# CommitV1_0.net
KiCad netlist of a schematic drawn in Altium Designer
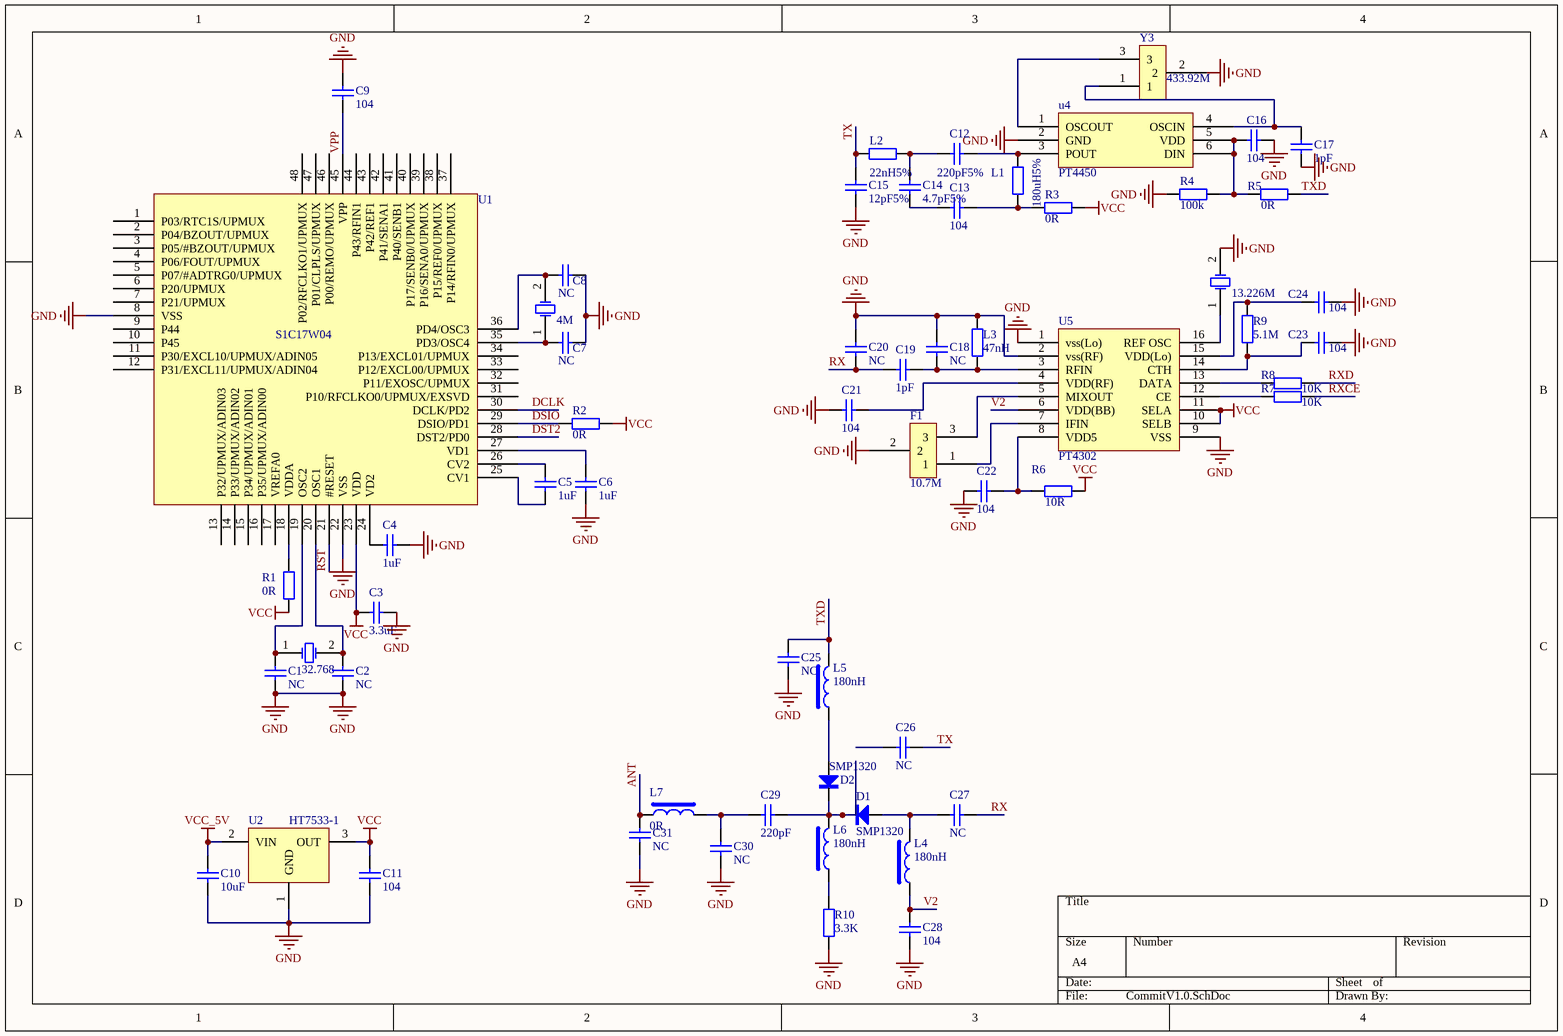
[diagram p0: CommitV1.0.SchDoc]

(export (version "E")
  (design (tool "Eeschema 10.0.6"))
  (components
    (comp (ref "C1")
      (value "NC")
      (footprint "0603")
      (description "Capacitor")
      (fields (field (name "PUBLISHER") "Altium Limited"))
      (libsource (lib "Miscellaneous Devices") (part "Cap"))
    )
    (comp (ref "C2")
      (value "NC")
      (footprint "0603")
      (description "Capacitor")
      (fields (field (name "PUBLISHER") "Altium Limited"))
      (libsource (lib "Miscellaneous Devices") (part "Cap"))
    )
    (comp (ref "C3")
      (value "3.3uF")
      (footprint "0603")
      (description "Capacitor")
      (fields (field (name "PUBLISHER") "Altium Limited"))
      (libsource (lib "Miscellaneous Devices") (part "Cap"))
    )
    (comp (ref "C4")
      (value "1uF")
      (footprint "0603")
      (description "Capacitor")
      (fields (field (name "PUBLISHER") "Altium Limited"))
      (libsource (lib "Miscellaneous Devices") (part "Cap"))
    )
    (comp (ref "C5")
      (value "1uF")
      (footprint "0603")
      (description "Capacitor")
      (fields (field (name "PUBLISHER") "Altium Limited"))
      (libsource (lib "Miscellaneous Devices") (part "Cap"))
    )
    (comp (ref "C6")
      (value "1uF")
      (footprint "0603")
      (description "Capacitor")
      (fields (field (name "PUBLISHER") "Altium Limited"))
      (libsource (lib "Miscellaneous Devices") (part "Cap"))
    )
    (comp (ref "C7")
      (value "NC")
      (footprint "0603")
      (description "Capacitor")
      (fields (field (name "PUBLISHER") "Altium Limited"))
      (libsource (lib "Miscellaneous Devices") (part "Cap"))
    )
    (comp (ref "C8")
      (value "NC")
      (footprint "0603")
      (description "Capacitor")
      (fields (field (name "PUBLISHER") "Altium Limited"))
      (libsource (lib "Miscellaneous Devices") (part "Cap"))
    )
    (comp (ref "C9")
      (value "104")
      (footprint "0603")
      (description "Capacitor")
      (fields (field (name "PUBLISHER") "Altium Limited"))
      (libsource (lib "Miscellaneous Devices") (part "Cap"))
    )
    (comp (ref "C10")
      (value "10uF")
      (footprint "0603")
      (description "Capacitor")
      (fields (field (name "PUBLISHER") "Altium Limited"))
      (libsource (lib "Miscellaneous Devices") (part "Cap"))
    )
    (comp (ref "C11")
      (value "104")
      (footprint "0603")
      (description "Capacitor")
      (fields (field (name "PUBLISHER") "Altium Limited"))
      (libsource (lib "Miscellaneous Devices") (part "Cap"))
    )
    (comp (ref "C12")
      (value "220pF5%")
      (footprint "0603")
      (description "Capacitor")
      (fields (field (name "PUBLISHER") "Altium Limited"))
      (libsource (lib "Miscellaneous Devices") (part "Cap"))
    )
    (comp (ref "C13")
      (value "104")
      (footprint "0603")
      (description "Capacitor")
      (fields (field (name "PUBLISHER") "Altium Limited"))
      (libsource (lib "Miscellaneous Devices") (part "Cap"))
    )
    (comp (ref "C14")
      (value "4.7pF5%")
      (footprint "0603")
      (description "Capacitor")
      (fields (field (name "PUBLISHER") "Altium Limited"))
      (libsource (lib "Miscellaneous Devices") (part "Cap"))
    )
    (comp (ref "C15")
      (value "12pF5%")
      (footprint "0603")
      (description "Capacitor")
      (fields (field (name "PUBLISHER") "Altium Limited"))
      (libsource (lib "Miscellaneous Devices") (part "Cap"))
    )
    (comp (ref "C16")
      (value "104")
      (footprint "0603")
      (description "Capacitor")
      (fields (field (name "PUBLISHER") "Altium Limited"))
      (libsource (lib "Miscellaneous Devices") (part "Cap"))
    )
    (comp (ref "C17")
      (value "1pF")
      (footprint "0603")
      (description "Capacitor")
      (fields (field (name "PUBLISHER") "Altium Limited"))
      (libsource (lib "Miscellaneous Devices") (part "Cap"))
    )
    (comp (ref "C18")
      (value "NC")
      (footprint "0603")
      (description "Capacitor")
      (fields (field (name "PUBLISHER") "Altium Limited"))
      (libsource (lib "Miscellaneous Devices") (part "Cap"))
    )
    (comp (ref "C19")
      (value "1pF")
      (footprint "0603")
      (description "Capacitor")
      (fields (field (name "PUBLISHER") "Altium Limited"))
      (libsource (lib "Miscellaneous Devices") (part "Cap"))
    )
    (comp (ref "C20")
      (value "NC")
      (footprint "0603")
      (description "Capacitor")
      (fields (field (name "PUBLISHER") "Altium Limited"))
      (libsource (lib "Miscellaneous Devices") (part "Cap"))
    )
    (comp (ref "C21")
      (value "104")
      (footprint "0603")
      (description "Capacitor")
      (fields (field (name "PUBLISHER") "Altium Limited"))
      (libsource (lib "Miscellaneous Devices") (part "Cap"))
    )
    (comp (ref "C22")
      (value "104")
      (footprint "0603")
      (description "Capacitor")
      (fields (field (name "PUBLISHER") "Altium Limited"))
      (libsource (lib "Miscellaneous Devices") (part "Cap"))
    )
    (comp (ref "C23")
      (value "104")
      (footprint "0603")
      (description "Capacitor")
      (fields (field (name "PUBLISHER") "Altium Limited"))
      (libsource (lib "Miscellaneous Devices") (part "Cap"))
    )
    (comp (ref "C24")
      (value "104")
      (footprint "0603")
      (description "Capacitor")
      (fields (field (name "PUBLISHER") "Altium Limited"))
      (libsource (lib "Miscellaneous Devices") (part "Cap"))
    )
    (comp (ref "C25")
      (value "NC")
      (footprint "0603")
      (description "Capacitor")
      (fields (field (name "PUBLISHER") "Altium Limited"))
      (libsource (lib "Miscellaneous Devices") (part "Cap"))
    )
    (comp (ref "C26")
      (value "NC")
      (footprint "0603")
      (description "Capacitor")
      (fields (field (name "PUBLISHER") "Altium Limited"))
      (libsource (lib "Miscellaneous Devices") (part "Cap"))
    )
    (comp (ref "C27")
      (value "NC")
      (footprint "0603")
      (description "Capacitor")
      (fields (field (name "PUBLISHER") "Altium Limited"))
      (libsource (lib "Miscellaneous Devices") (part "Cap"))
    )
    (comp (ref "C28")
      (value "104")
      (footprint "0603")
      (description "Capacitor")
      (fields (field (name "PUBLISHER") "Altium Limited"))
      (libsource (lib "Miscellaneous Devices") (part "Cap"))
    )
    (comp (ref "C29")
      (value "220pF")
      (footprint "0603")
      (description "Capacitor")
      (fields (field (name "PUBLISHER") "Altium Limited"))
      (libsource (lib "Miscellaneous Devices") (part "Cap"))
    )
    (comp (ref "C30")
      (value "NC")
      (footprint "0603")
      (description "Capacitor")
      (fields (field (name "PUBLISHER") "Altium Limited"))
      (libsource (lib "Miscellaneous Devices") (part "Cap"))
    )
    (comp (ref "C31")
      (value "NC")
      (footprint "0603")
      (description "Capacitor")
      (fields (field (name "PUBLISHER") "Altium Limited"))
      (libsource (lib "Miscellaneous Devices") (part "Cap"))
    )
    (comp (ref "D1")
      (value "SMP1320")
      (footprint "0603")
      (description "diode")
      (libsource (lib "dajiang SCH -DXP") (part "DIODE"))
    )
    (comp (ref "D2")
      (value "SMP1320")
      (footprint "0603")
      (description "diode")
      (libsource (lib "") (part "DIODE_1"))
    )
    (comp (ref "F1") (value "10.7M") (footprint "PT4450 XTAL") (libsource (lib "MYSHC") (part "Filter")))
    (comp (ref "L1")
      (value "180uH5%")
      (footprint "0603")
      (description "Resistor")
      (fields (field (name "PUBLISHER") "Altium Limited"))
      (libsource (lib "") (part "Res2_1"))
    )
    (comp (ref "L2")
      (value "22nH5%")
      (footprint "0603")
      (description "Resistor")
      (fields (field (name "PUBLISHER") "Altium Limited"))
      (libsource (lib "") (part "Res2_2"))
    )
    (comp (ref "L3")
      (value "47nH")
      (footprint "0603")
      (description "Resistor")
      (fields (field (name "PUBLISHER") "Altium Limited"))
      (libsource (lib "") (part "Res2_3"))
    )
    (comp (ref "L4")
      (value "180nH")
      (footprint "0603")
      (description "Inductor")
      (libsource (lib "dajiang SCH -DXP") (part "L"))
    )
    (comp (ref "L5")
      (value "180nH")
      (footprint "0603")
      (description "Inductor")
      (libsource (lib "dajiang SCH -DXP") (part "L"))
    )
    (comp (ref "L6")
      (value "180nH")
      (footprint "0603")
      (description "Inductor")
      (libsource (lib "dajiang SCH -DXP") (part "L"))
    )
    (comp (ref "L7")
      (value "0R")
      (footprint "0603")
      (description "Inductor")
      (libsource (lib "") (part "L_1"))
    )
    (comp (ref "R1")
      (value "0R")
      (footprint "0603")
      (description "Resistor")
      (fields (field (name "PUBLISHER") "Altium Limited"))
      (libsource (lib "") (part "Res2_1"))
    )
    (comp (ref "R2")
      (value "0R")
      (footprint "0603")
      (description "Resistor")
      (fields (field (name "PUBLISHER") "Altium Limited"))
      (libsource (lib "Miscellaneous Devices") (part "Res2"))
    )
    (comp (ref "R3")
      (value "0R")
      (footprint "0603")
      (description "Resistor")
      (fields (field (name "PUBLISHER") "Altium Limited"))
      (libsource (lib "Miscellaneous Devices") (part "Res2"))
    )
    (comp (ref "R4")
      (value "100k")
      (footprint "0603")
      (description "Resistor")
      (fields (field (name "PUBLISHER") "Altium Limited"))
      (libsource (lib "Miscellaneous Devices") (part "Res2"))
    )
    (comp (ref "R5")
      (value "0R")
      (footprint "0603")
      (description "Resistor")
      (fields (field (name "PUBLISHER") "Altium Limited"))
      (libsource (lib "Miscellaneous Devices") (part "Res2"))
    )
    (comp (ref "R6")
      (value "10R")
      (footprint "0603")
      (description "Resistor")
      (fields (field (name "PUBLISHER") "Altium Limited"))
      (libsource (lib "Miscellaneous Devices") (part "Res2"))
    )
    (comp (ref "R7")
      (value "10K")
      (footprint "0603")
      (description "Resistor")
      (fields (field (name "PUBLISHER") "Altium Limited"))
      (libsource (lib "Miscellaneous Devices") (part "Res2"))
    )
    (comp (ref "R8")
      (value "10K")
      (footprint "0603")
      (description "Resistor")
      (fields (field (name "PUBLISHER") "Altium Limited"))
      (libsource (lib "Miscellaneous Devices") (part "Res2"))
    )
    (comp (ref "R9")
      (value "5.1M")
      (footprint "0603")
      (description "Resistor")
      (fields (field (name "PUBLISHER") "Altium Limited"))
      (libsource (lib "") (part "Res2_1"))
    )
    (comp (ref "R10")
      (value "3.3K")
      (footprint "0603")
      (description "Resistor")
      (fields (field (name "PUBLISHER") "Altium Limited"))
      (libsource (lib "") (part "Res2_1"))
    )
    (comp (ref "U1") (value "S1C17W04") (libsource (lib "MYSHC") (part "TQFP12-48PIN")))
    (comp (ref "U2") (value "HT7533-1") (footprint "3A5A3D") (libsource (lib "mylib") (part "HT7533-1")))
    (comp (ref "u4") (value "PT4450") (footprint "PT4450") (libsource (lib "MYSHC") (part "PT4450")))
    (comp (ref "U5") (value "PT4302") (footprint "PT4302") (libsource (lib "MYSHC") (part "PT4302")))
    (comp (ref "Y1")
      (value "32.768")
      (footprint "XTAL-FC135")
      (description "Crystal Oscillator")
      (libsource (lib "DT-852A(3)") (part "XTAL"))
    )
    (comp (ref "Y2")
      (value "4M")
      (description "Crystal Oscillator")
      (libsource (lib "DT-852A(3)") (part "XTAL"))
    )
    (comp (ref "Y3") (value "433.92M") (libsource (lib "MYSHC") (part "PT4450-XTAL")))
    (comp (ref "Y4")
      (value "13.226M")
      (footprint "PT4306 XTAL")
      (description "Crystal Oscillator")
      (libsource (lib "DT-852A(3)") (part "XTAL"))
    )
  )
  (nets
    (net (code "1") (name "/ANT") (class "Default")
      (node (ref "C31") (pin "1") (pinfunction "1_1") (pintype "passive"))
      (node (ref "L7") (pin "1") (pinfunction "1_1") (pintype "passive"))
    )
    (net (code "2") (name "/DCLK") (class "Default")
      (node (ref "U1") (pin "30") (pinfunction "DCLK/PD2_30") (pintype "passive"))
    )
    (net (code "3") (name "/DSIO") (class "Default")
      (node (ref "R2") (pin "2") (pinfunction "2_2") (pintype "passive"))
      (node (ref "U1") (pin "29") (pinfunction "DSIO/PD1_29") (pintype "passive"))
    )
    (net (code "4") (name "/DST2") (class "Default")
      (node (ref "U1") (pin "28") (pinfunction "DST2/PD0_28") (pintype "passive"))
    )
    (net (code "5") (name "/RST") (class "Default")
      (node (ref "U1") (pin "21") (pinfunction "#RESET_21") (pintype "passive"))
    )
    (net (code "6") (name "/RX") (class "Default")
      (node (ref "C19") (pin "1") (pinfunction "1_1") (pintype "passive"))
      (node (ref "C20") (pin "1") (pinfunction "1_1") (pintype "passive"))
      (node (ref "C27") (pin "2") (pinfunction "2_2") (pintype "passive"))
    )
    (net (code "7") (name "/RXCE") (class "Default")
      (node (ref "R7") (pin "1") (pinfunction "1_1") (pintype "passive"))
    )
    (net (code "8") (name "/RXD") (class "Default")
      (node (ref "R8") (pin "1") (pinfunction "1_1") (pintype "passive"))
    )
    (net (code "9") (name "/TX") (class "Default")
      (node (ref "C15") (pin "2") (pinfunction "2_2") (pintype "passive"))
      (node (ref "C26") (pin "2") (pinfunction "2_2") (pintype "passive"))
      (node (ref "L2") (pin "1") (pinfunction "1_1") (pintype "passive"))
    )
    (net (code "10") (name "/TXD") (class "Default")
      (node (ref "C25") (pin "1") (pinfunction "1_1") (pintype "passive"))
      (node (ref "L5") (pin "2") (pinfunction "2_2") (pintype "passive"))
      (node (ref "R5") (pin "1") (pinfunction "1_1") (pintype "passive"))
    )
    (net (code "11") (name "/V2") (class "Default")
      (node (ref "C28") (pin "2") (pinfunction "2_2") (pintype "passive"))
      (node (ref "L4") (pin "1") (pinfunction "1_1") (pintype "passive"))
      (node (ref "U5") (pin "6") (pinfunction "VDD(BB)_6") (pintype "passive"))
    )
    (net (code "12") (name "/VPP") (class "Default")
      (node (ref "C9") (pin "1") (pinfunction "1_1") (pintype "passive"))
      (node (ref "U1") (pin "45") (pinfunction "VPP_45") (pintype "passive"))
    )
    (net (code "13") (name "GND") (class "Default")
      (node (ref "C1") (pin "1") (pinfunction "1_1") (pintype "passive"))
      (node (ref "C10") (pin "2") (pinfunction "2_2") (pintype "passive"))
      (node (ref "C11") (pin "2") (pinfunction "2_2") (pintype "passive"))
      (node (ref "C15") (pin "1") (pinfunction "1_1") (pintype "passive"))
      (node (ref "C16") (pin "1") (pinfunction "1_1") (pintype "passive"))
      (node (ref "C17") (pin "2") (pinfunction "2_2") (pintype "passive"))
      (node (ref "C18") (pin "1") (pinfunction "1_1") (pintype "passive"))
      (node (ref "C2") (pin "1") (pinfunction "1_1") (pintype "passive"))
      (node (ref "C20") (pin "2") (pinfunction "2_2") (pintype "passive"))
      (node (ref "C21") (pin "2") (pinfunction "2_2") (pintype "passive"))
      (node (ref "C22") (pin "2") (pinfunction "2_2") (pintype "passive"))
      (node (ref "C23") (pin "1") (pinfunction "1_1") (pintype "passive"))
      (node (ref "C24") (pin "1") (pinfunction "1_1") (pintype "passive"))
      (node (ref "C25") (pin "2") (pinfunction "2_2") (pintype "passive"))
      (node (ref "C28") (pin "1") (pinfunction "1_1") (pintype "passive"))
      (node (ref "C3") (pin "1") (pinfunction "1_1") (pintype "passive"))
      (node (ref "C30") (pin "2") (pinfunction "2_2") (pintype "passive"))
      (node (ref "C31") (pin "2") (pinfunction "2_2") (pintype "passive"))
      (node (ref "C4") (pin "2") (pinfunction "2_2") (pintype "passive"))
      (node (ref "C6") (pin "2") (pinfunction "2_2") (pintype "passive"))
      (node (ref "C7") (pin "1") (pinfunction "1_1") (pintype "passive"))
      (node (ref "C8") (pin "1") (pinfunction "1_1") (pintype "passive"))
      (node (ref "C9") (pin "2") (pinfunction "2_2") (pintype "passive"))
      (node (ref "F1") (pin "2") (pinfunction "2_2") (pintype "passive"))
      (node (ref "L3") (pin "2") (pinfunction "2_2") (pintype "passive"))
      (node (ref "R10") (pin "2") (pinfunction "2_2") (pintype "passive"))
      (node (ref "R4") (pin "2") (pinfunction "2_2") (pintype "passive"))
      (node (ref "U1") (pin "22") (pinfunction "VSS_22") (pintype "passive"))
      (node (ref "U1") (pin "8") (pinfunction "VSS_8") (pintype "passive"))
      (node (ref "U2") (pin "1") (pinfunction "GND_1") (pintype "passive"))
      (node (ref "U5") (pin "1") (pinfunction "vss(Lo)_1") (pintype "passive"))
      (node (ref "U5") (pin "2") (pinfunction "vss(RF)_2") (pintype "passive"))
      (node (ref "U5") (pin "9") (pinfunction "VSS_9") (pintype "passive"))
      (node (ref "Y3") (pin "2") (pinfunction "2_2") (pintype "passive"))
      (node (ref "Y4") (pin "2") (pinfunction "OSC2_2") (pintype "passive"))
      (node (ref "u4") (pin "2") (pinfunction "GND_2") (pintype "passive"))
    )
    (net (code "14") (name "Net-(C12-Pad1)") (class "Default")
      (node (ref "C12") (pin "1") (pinfunction "1_1") (pintype "passive"))
      (node (ref "C14") (pin "2") (pinfunction "2_2") (pintype "passive"))
      (node (ref "L2") (pin "2") (pinfunction "2_2") (pintype "passive"))
    )
    (net (code "15") (name "Net-(C13-Pad1)") (class "Default")
      (node (ref "C13") (pin "1") (pinfunction "1_1") (pintype "passive"))
      (node (ref "C14") (pin "1") (pinfunction "1_1") (pintype "passive"))
    )
    (net (code "16") (name "Net-(C13-Pad2)") (class "Default")
      (node (ref "C13") (pin "2") (pinfunction "2_2") (pintype "passive"))
      (node (ref "L1") (pin "2") (pinfunction "2_2") (pintype "passive"))
      (node (ref "R3") (pin "2") (pinfunction "2_2") (pintype "passive"))
    )
    (net (code "17") (name "Net-(C27-Pad1)") (class "Default")
      (node (ref "C27") (pin "1") (pinfunction "1_1") (pintype "passive"))
      (node (ref "D1") (pin "1") (pinfunction "1_1") (pintype "passive"))
      (node (ref "L4") (pin "2") (pinfunction "2_2") (pintype "passive"))
    )
    (net (code "18") (name "Net-(C29-Pad1)") (class "Default")
      (node (ref "C29") (pin "1") (pinfunction "1_1") (pintype "passive"))
      (node (ref "D1") (pin "2") (pinfunction "2_2") (pintype "passive"))
      (node (ref "D2") (pin "2") (pinfunction "2_2") (pintype "passive"))
      (node (ref "L6") (pin "2") (pinfunction "2_2") (pintype "passive"))
    )
    (net (code "19") (name "Net-(C29-Pad2)") (class "Default")
      (node (ref "C29") (pin "2") (pinfunction "2_2") (pintype "passive"))
      (node (ref "C30") (pin "1") (pinfunction "1_1") (pintype "passive"))
      (node (ref "L7") (pin "2") (pinfunction "2_2") (pintype "passive"))
    )
    (net (code "20") (name "Net-(D2-Pad1)") (class "Default")
      (node (ref "D2") (pin "1") (pinfunction "1_1") (pintype "passive"))
      (node (ref "L5") (pin "1") (pinfunction "1_1") (pintype "passive"))
    )
    (net (code "21") (name "Net-(L6-Pad1)") (class "Default")
      (node (ref "L6") (pin "1") (pinfunction "1_1") (pintype "passive"))
      (node (ref "R10") (pin "1") (pinfunction "1_1") (pintype "passive"))
    )
    (net (code "22") (name "Net-(U1-CV1)") (class "Default")
      (node (ref "C5") (pin "1") (pinfunction "1_1") (pintype "passive"))
      (node (ref "U1") (pin "25") (pinfunction "CV1_25") (pintype "passive"))
    )
    (net (code "23") (name "Net-(U1-CV2)") (class "Default")
      (node (ref "C5") (pin "2") (pinfunction "2_2") (pintype "passive"))
      (node (ref "U1") (pin "26") (pinfunction "CV2_26") (pintype "passive"))
    )
    (net (code "24") (name "Net-(U1-OSC1)") (class "Default")
      (node (ref "C2") (pin "2") (pinfunction "2_2") (pintype "passive"))
      (node (ref "U1") (pin "20") (pinfunction "OSC1_20") (pintype "passive"))
      (node (ref "Y1") (pin "2") (pinfunction "OSC2_2") (pintype "passive"))
    )
    (net (code "25") (name "Net-(U1-OSC2)") (class "Default")
      (node (ref "C1") (pin "2") (pinfunction "2_2") (pintype "passive"))
      (node (ref "U1") (pin "19") (pinfunction "OSC2_19") (pintype "passive"))
      (node (ref "Y1") (pin "1") (pinfunction "OSC1_1") (pintype "passive"))
    )
    (net (code "26") (name "Net-(U1-PD3{slash}OSC4)") (class "Default")
      (node (ref "C7") (pin "2") (pinfunction "2_2") (pintype "passive"))
      (node (ref "U1") (pin "35") (pinfunction "PD3/OSC4_35") (pintype "passive"))
      (node (ref "Y2") (pin "1") (pinfunction "OSC1_1") (pintype "passive"))
    )
    (net (code "27") (name "Net-(U1-PD4{slash}OSC3)") (class "Default")
      (node (ref "C8") (pin "2") (pinfunction "2_2") (pintype "passive"))
      (node (ref "U1") (pin "36") (pinfunction "PD4/OSC3_36") (pintype "passive"))
      (node (ref "Y2") (pin "2") (pinfunction "OSC2_2") (pintype "passive"))
    )
    (net (code "28") (name "Net-(U1-VD1)") (class "Default")
      (node (ref "C6") (pin "1") (pinfunction "1_1") (pintype "passive"))
      (node (ref "U1") (pin "27") (pinfunction "VD1_27") (pintype "passive"))
    )
    (net (code "29") (name "Net-(U1-VD2)") (class "Default")
      (node (ref "C4") (pin "1") (pinfunction "1_1") (pintype "passive"))
      (node (ref "U1") (pin "24") (pinfunction "VD2_24") (pintype "passive"))
    )
    (net (code "30") (name "Net-(U1-VDDA)") (class "Default")
      (node (ref "R1") (pin "1") (pinfunction "1_1") (pintype "passive"))
      (node (ref "U1") (pin "18") (pinfunction "VDDA_18") (pintype "passive"))
    )
    (net (code "31") (name "Net-(U5-CE)") (class "Default")
      (node (ref "R7") (pin "2") (pinfunction "2_2") (pintype "passive"))
      (node (ref "U5") (pin "12") (pinfunction "CE_12") (pintype "passive"))
    )
    (net (code "32") (name "Net-(U5-CTH)") (class "Default")
      (node (ref "C23") (pin "2") (pinfunction "2_2") (pintype "passive"))
      (node (ref "R9") (pin "2") (pinfunction "2_2") (pintype "passive"))
      (node (ref "U5") (pin "14") (pinfunction "CTH_14") (pintype "passive"))
    )
    (net (code "33") (name "Net-(U5-DATA)") (class "Default")
      (node (ref "R8") (pin "2") (pinfunction "2_2") (pintype "passive"))
      (node (ref "U5") (pin "13") (pinfunction "DATA_13") (pintype "passive"))
    )
    (net (code "34") (name "Net-(U5-IFIN)") (class "Default")
      (node (ref "F1") (pin "1") (pinfunction "1_1") (pintype "passive"))
      (node (ref "U5") (pin "7") (pinfunction "IFIN_7") (pintype "passive"))
    )
    (net (code "35") (name "Net-(U5-MIXOUT)") (class "Default")
      (node (ref "F1") (pin "3") (pinfunction "3_3") (pintype "passive"))
      (node (ref "U5") (pin "5") (pinfunction "MIXOUT_5") (pintype "passive"))
    )
    (net (code "36") (name "Net-(U5-REF_OSC)") (class "Default")
      (node (ref "U5") (pin "16") (pinfunction "REF_OSC_16") (pintype "passive"))
      (node (ref "Y4") (pin "1") (pinfunction "OSC1_1") (pintype "passive"))
    )
    (net (code "37") (name "Net-(U5-RFIN)") (class "Default")
      (node (ref "C18") (pin "2") (pinfunction "2_2") (pintype "passive"))
      (node (ref "C19") (pin "2") (pinfunction "2_2") (pintype "passive"))
      (node (ref "L3") (pin "1") (pinfunction "1_1") (pintype "passive"))
      (node (ref "U5") (pin "3") (pinfunction "RFIN_3") (pintype "passive"))
    )
    (net (code "38") (name "Net-(U5-VDD(Lo))") (class "Default")
      (node (ref "C24") (pin "2") (pinfunction "2_2") (pintype "passive"))
      (node (ref "R9") (pin "1") (pinfunction "1_1") (pintype "passive"))
      (node (ref "U5") (pin "15") (pinfunction "VDD(Lo)_15") (pintype "passive"))
    )
    (net (code "39") (name "Net-(U5-VDD(RF))") (class "Default")
      (node (ref "C21") (pin "1") (pinfunction "1_1") (pintype "passive"))
      (node (ref "U5") (pin "4") (pinfunction "VDD(RF)_4") (pintype "passive"))
    )
    (net (code "40") (name "Net-(U5-VDD5)") (class "Default")
      (node (ref "C22") (pin "1") (pinfunction "1_1") (pintype "passive"))
      (node (ref "R6") (pin "2") (pinfunction "2_2") (pintype "passive"))
      (node (ref "U5") (pin "8") (pinfunction "VDD5_8") (pintype "passive"))
    )
    (net (code "41") (name "Net-(u4-DIN)") (class "Default")
      (node (ref "C16") (pin "2") (pinfunction "2_2") (pintype "passive"))
      (node (ref "R4") (pin "1") (pinfunction "1_1") (pintype "passive"))
      (node (ref "R5") (pin "2") (pinfunction "2_2") (pintype "passive"))
      (node (ref "u4") (pin "5") (pinfunction "VDD_5") (pintype "passive"))
      (node (ref "u4") (pin "6") (pinfunction "DIN_6") (pintype "passive"))
    )
    (net (code "42") (name "Net-(u4-OSCIN)") (class "Default")
      (node (ref "C17") (pin "1") (pinfunction "1_1") (pintype "passive"))
      (node (ref "Y3") (pin "1") (pinfunction "1_1") (pintype "passive"))
      (node (ref "u4") (pin "4") (pinfunction "OSCIN_4") (pintype "passive"))
    )
    (net (code "43") (name "Net-(u4-OSCOUT)") (class "Default")
      (node (ref "Y3") (pin "3") (pinfunction "3_3") (pintype "passive"))
      (node (ref "u4") (pin "1") (pinfunction "OSCOUT_1") (pintype "passive"))
    )
    (net (code "44") (name "Net-(u4-POUT)") (class "Default")
      (node (ref "C12") (pin "2") (pinfunction "2_2") (pintype "passive"))
      (node (ref "L1") (pin "1") (pinfunction "1_1") (pintype "passive"))
      (node (ref "u4") (pin "3") (pinfunction "POUT_3") (pintype "passive"))
    )
    (net (code "45") (name "VCC") (class "Default")
      (node (ref "C11") (pin "1") (pinfunction "1_1") (pintype "passive"))
      (node (ref "C3") (pin "2") (pinfunction "2_2") (pintype "passive"))
      (node (ref "R1") (pin "2") (pinfunction "2_2") (pintype "passive"))
      (node (ref "R2") (pin "1") (pinfunction "1_1") (pintype "passive"))
      (node (ref "R3") (pin "1") (pinfunction "1_1") (pintype "passive"))
      (node (ref "R6") (pin "1") (pinfunction "1_1") (pintype "passive"))
      (node (ref "U1") (pin "23") (pinfunction "VDD_23") (pintype "passive"))
      (node (ref "U2") (pin "3") (pinfunction "OUT_3") (pintype "passive"))
      (node (ref "U5") (pin "10") (pinfunction "SELB_10") (pintype "passive"))
      (node (ref "U5") (pin "11") (pinfunction "SELA_11") (pintype "passive"))
    )
    (net (code "46") (name "VCC_5V") (class "Default")
      (node (ref "C10") (pin "1") (pinfunction "1_1") (pintype "passive"))
      (node (ref "U2") (pin "2") (pinfunction "VIN_2") (pintype "passive"))
    )
    (net (code "47") (name "unconnected-(C26-Pad1)") (class "Default")
      (node (ref "C26") (pin "1") (pinfunction "1_1") (pintype "passive"))
    )
    (net (code "48") (name "unconnected-(U1-P00{slash}REMO{slash}UPMUX-Pad46)") (class "Default")
      (node (ref "U1") (pin "46") (pinfunction "P00/REMO/UPMUX_46") (pintype "passive"))
    )
    (net (code "49") (name "unconnected-(U1-P01{slash}CLPLS{slash}UPMUX-Pad47)") (class "Default")
      (node (ref "U1") (pin "47") (pinfunction "P01/CLPLS/UPMUX_47") (pintype "passive"))
    )
    (net (code "50") (name "unconnected-(U1-P02{slash}RFCLKO1{slash}UPMUX-Pad48)") (class "Default")
      (node (ref "U1") (pin "48") (pinfunction "P02/RFCLKO1/UPMUX_48") (pintype "passive"))
    )
    (net (code "51") (name "unconnected-(U1-P03{slash}RTC1S{slash}UPMUX-Pad1)") (class "Default")
      (node (ref "U1") (pin "1") (pinfunction "P03/RTC1S/UPMUX_1") (pintype "passive"))
    )
    (net (code "52") (name "unconnected-(U1-P04{slash}BZOUT{slash}UPMUX-Pad2)") (class "Default")
      (node (ref "U1") (pin "2") (pinfunction "P04/BZOUT/UPMUX_2") (pintype "passive"))
    )
    (net (code "53") (name "unconnected-(U1-P05{slash}#BZOUT{slash}UPMUX-Pad3)") (class "Default")
      (node (ref "U1") (pin "3") (pinfunction "P05/#BZOUT/UPMUX_3") (pintype "passive"))
    )
    (net (code "54") (name "unconnected-(U1-P06{slash}FOUT{slash}UPMUX-Pad4)") (class "Default")
      (node (ref "U1") (pin "4") (pinfunction "P06/FOUT/UPMUX_4") (pintype "passive"))
    )
    (net (code "55") (name "unconnected-(U1-P07{slash}#ADTRG0{slash}UPMUX-Pad5)") (class "Default")
      (node (ref "U1") (pin "5") (pinfunction "P07/#ADTRG0/UPMUX_5") (pintype "passive"))
    )
    (net (code "56") (name "unconnected-(U1-P10{slash}RFCLKO0{slash}UPMUX{slash}EXSVD-Pad31)") (class "Default")
      (node (ref "U1") (pin "31") (pinfunction "P10/RFCLKO0/UPMUX/EXSVD_31") (pintype "passive"))
    )
    (net (code "57") (name "unconnected-(U1-P11{slash}EXOSC{slash}UPMUX-Pad32)") (class "Default")
      (node (ref "U1") (pin "32") (pinfunction "P11/EXOSC/UPMUX_32") (pintype "passive"))
    )
    (net (code "58") (name "unconnected-(U1-P12{slash}EXCL00{slash}UPMUX-Pad33)") (class "Default")
      (node (ref "U1") (pin "33") (pinfunction "P12/EXCL00/UPMUX_33") (pintype "passive"))
    )
    (net (code "59") (name "unconnected-(U1-P13{slash}EXCL01{slash}UPMUX-Pad34)") (class "Default")
      (node (ref "U1") (pin "34") (pinfunction "P13/EXCL01/UPMUX_34") (pintype "passive"))
    )
    (net (code "60") (name "unconnected-(U1-P14{slash}RFIN0{slash}UPMUX-Pad37)") (class "Default")
      (node (ref "U1") (pin "37") (pinfunction "P14/RFIN0/UPMUX_37") (pintype "passive"))
    )
    (net (code "61") (name "unconnected-(U1-P15{slash}REF0{slash}UPMUX-Pad38)") (class "Default")
      (node (ref "U1") (pin "38") (pinfunction "P15/REF0/UPMUX_38") (pintype "passive"))
    )
    (net (code "62") (name "unconnected-(U1-P16{slash}SENA0{slash}UPMUX-Pad39)") (class "Default")
      (node (ref "U1") (pin "39") (pinfunction "P16/SENA0/UPMUX_39") (pintype "passive"))
    )
    (net (code "63") (name "unconnected-(U1-P17{slash}SENB0{slash}UPMUX-Pad40)") (class "Default")
      (node (ref "U1") (pin "40") (pinfunction "P17/SENB0/UPMUX_40") (pintype "passive"))
    )
    (net (code "64") (name "unconnected-(U1-P20{slash}UPMUX-Pad6)") (class "Default")
      (node (ref "U1") (pin "6") (pinfunction "P20/UPMUX_6") (pintype "passive"))
    )
    (net (code "65") (name "unconnected-(U1-P21{slash}UPMUX-Pad7)") (class "Default")
      (node (ref "U1") (pin "7") (pinfunction "P21/UPMUX_7") (pintype "passive"))
    )
    (net (code "66") (name "unconnected-(U1-P30{slash}EXCL10{slash}UPMUX{slash}ADIN05-Pad11)") (class "Default")
      (node (ref "U1") (pin "11") (pinfunction "P30/EXCL10/UPMUX/ADIN05_11") (pintype "passive"))
    )
    (net (code "67") (name "unconnected-(U1-P31{slash}EXCL11{slash}UPMUX{slash}ADIN04-Pad12)") (class "Default")
      (node (ref "U1") (pin "12") (pinfunction "P31/EXCL11/UPMUX/ADIN04_12") (pintype "passive"))
    )
    (net (code "68") (name "unconnected-(U1-P32{slash}UPMUX{slash}ADIN03-Pad13)") (class "Default")
      (node (ref "U1") (pin "13") (pinfunction "P32/UPMUX/ADIN03_13") (pintype "passive"))
    )
    (net (code "69") (name "unconnected-(U1-P33{slash}UPMUX{slash}ADIN02-Pad14)") (class "Default")
      (node (ref "U1") (pin "14") (pinfunction "P33/UPMUX/ADIN02_14") (pintype "passive"))
    )
    (net (code "70") (name "unconnected-(U1-P34{slash}UPMUX{slash}ADIN01-Pad15)") (class "Default")
      (node (ref "U1") (pin "15") (pinfunction "P34/UPMUX/ADIN01_15") (pintype "passive"))
    )
    (net (code "71") (name "unconnected-(U1-P35{slash}UPMUX{slash}ADIN00-Pad16)") (class "Default")
      (node (ref "U1") (pin "16") (pinfunction "P35/UPMUX/ADIN00_16") (pintype "passive"))
    )
    (net (code "72") (name "unconnected-(U1-P40{slash}SENB1-Pad41)") (class "Default")
      (node (ref "U1") (pin "41") (pinfunction "P40/SENB1_41") (pintype "passive"))
    )
    (net (code "73") (name "unconnected-(U1-P41{slash}SENA1-Pad42)") (class "Default")
      (node (ref "U1") (pin "42") (pinfunction "P41/SENA1_42") (pintype "passive"))
    )
    (net (code "74") (name "unconnected-(U1-P42{slash}REF1-Pad43)") (class "Default")
      (node (ref "U1") (pin "43") (pinfunction "P42/REF1_43") (pintype "passive"))
    )
    (net (code "75") (name "unconnected-(U1-P43{slash}RFIN1-Pad44)") (class "Default")
      (node (ref "U1") (pin "44") (pinfunction "P43/RFIN1_44") (pintype "passive"))
    )
    (net (code "76") (name "unconnected-(U1-P44-Pad9)") (class "Default")
      (node (ref "U1") (pin "9") (pinfunction "P44_9") (pintype "passive"))
    )
    (net (code "77") (name "unconnected-(U1-P45-Pad10)") (class "Default")
      (node (ref "U1") (pin "10") (pinfunction "P45_10") (pintype "passive"))
    )
    (net (code "78") (name "unconnected-(U1-VREFA0-Pad17)") (class "Default")
      (node (ref "U1") (pin "17") (pinfunction "VREFA0_17") (pintype "passive"))
    )
  )
)
